# H_Power_feed.net
KiCad netlist of a schematic drawn in EAGLE
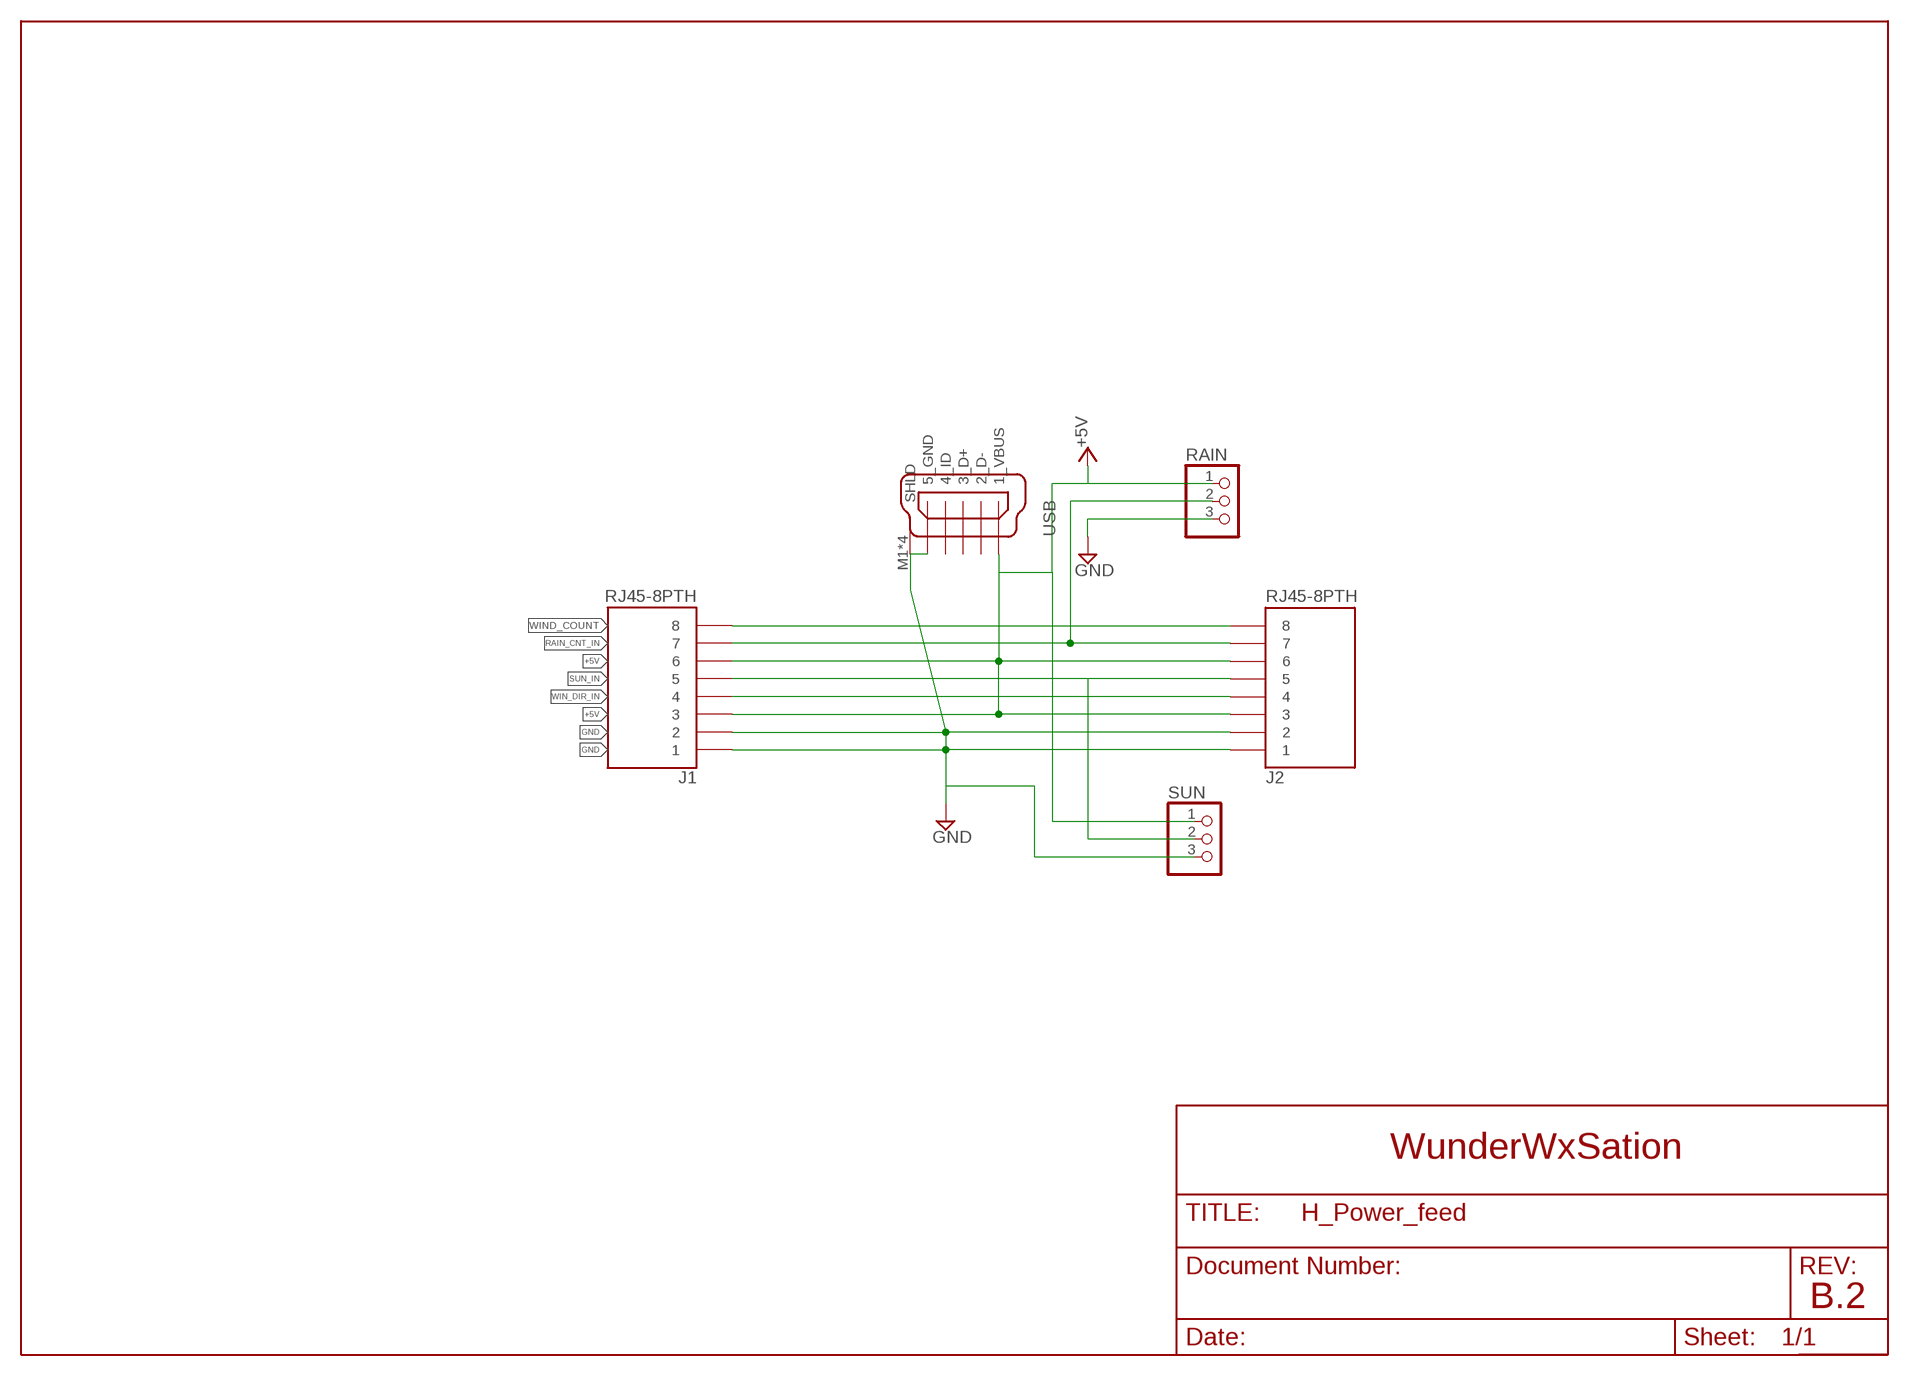
[diagram p0: schematic, sheet 1]

(export (version "E")
  (design (tool "Eeschema 10.0.6"))
  (components
    (comp (ref "J1")
      (value "RJ45-8PTH")
      (footprint "eagle-import:RJ45-8")
      (libsource (lib "eagle-import") (part "RJ45-8PTH"))
    )
    (comp (ref "J2")
      (value "RJ45-8PTH")
      (footprint "eagle-import:RJ45-8")
      (libsource (lib "eagle-import") (part "RJ45-8PTH"))
    )
    (comp (ref "RAIN")
      (value "PINHD-1X3MOLEX_KK")
      (footprint "eagle-import:1X3_MOLEX_KK")
      (libsource (lib "eagle-import") (part "PINHD-1X3MOLEX_KK"))
    )
    (comp (ref "SUN")
      (value "PINHD-1X3MOLEX_KK")
      (footprint "eagle-import:1X3_MOLEX_KK")
      (libsource (lib "eagle-import") (part "PINHD-1X3MOLEX_KK"))
    )
    (comp (ref "USB")
      (value "MINI-USB-32005-301")
      (footprint "eagle-import:32005-301")
      (libsource (lib "eagle-import") (part "MINI-USB-32005-301"))
    )
  )
  (nets
    (net (code "1") (name "+5V") (class "Default")
      (node (ref "J1") (pin "3") (pinfunction "3_3") (pintype "bidirectional"))
      (node (ref "J1") (pin "6") (pinfunction "6_6") (pintype "bidirectional"))
      (node (ref "J2") (pin "3") (pinfunction "3_3") (pintype "bidirectional"))
      (node (ref "J2") (pin "6") (pinfunction "6_6") (pintype "bidirectional"))
      (node (ref "RAIN") (pin "1") (pinfunction "1_1") (pintype "passive"))
      (node (ref "SUN") (pin "1") (pinfunction "1_1") (pintype "passive"))
      (node (ref "USB") (pin "1_VBUS") (pinfunction "1_VBUS_1_VBUS") (pintype "passive"))
    )
    (net (code "2") (name "GND") (class "Default")
      (node (ref "J1") (pin "1") (pinfunction "1_1") (pintype "bidirectional"))
      (node (ref "J1") (pin "2") (pinfunction "2_2") (pintype "bidirectional"))
      (node (ref "J2") (pin "1") (pinfunction "1_1") (pintype "bidirectional"))
      (node (ref "J2") (pin "2") (pinfunction "2_2") (pintype "bidirectional"))
      (node (ref "RAIN") (pin "3") (pinfunction "3_3") (pintype "passive"))
      (node (ref "SUN") (pin "3") (pinfunction "3_3") (pintype "passive"))
      (node (ref "USB") (pin "5_USB_GND") (pinfunction "5_GND_5_USB_GND") (pintype "passive"))
      (node (ref "USB") (pin "M1") (pinfunction "SHLD_M1") (pintype "passive"))
      (node (ref "USB") (pin "M2") (pinfunction "SHLD_M2") (pintype "passive"))
      (node (ref "USB") (pin "M3") (pinfunction "SHLD_M3") (pintype "passive"))
      (node (ref "USB") (pin "M4") (pinfunction "SHLD_M4") (pintype "passive"))
    )
    (net (code "3") (name "RAIN_CNT_IN") (class "Default")
      (node (ref "J1") (pin "7") (pinfunction "7_7") (pintype "bidirectional"))
      (node (ref "J2") (pin "7") (pinfunction "7_7") (pintype "bidirectional"))
      (node (ref "RAIN") (pin "2") (pinfunction "2_2") (pintype "passive"))
    )
    (net (code "4") (name "SUN_IN") (class "Default")
      (node (ref "J1") (pin "5") (pinfunction "5_5") (pintype "bidirectional"))
      (node (ref "J2") (pin "5") (pinfunction "5_5") (pintype "bidirectional"))
      (node (ref "SUN") (pin "2") (pinfunction "2_2") (pintype "passive"))
    )
    (net (code "5") (name "WIND_COUNT") (class "Default")
      (node (ref "J1") (pin "8") (pinfunction "8_8") (pintype "bidirectional"))
      (node (ref "J2") (pin "8") (pinfunction "8_8") (pintype "bidirectional"))
    )
    (net (code "6") (name "WIN_DIR_IN") (class "Default")
      (node (ref "J1") (pin "4") (pinfunction "4_4") (pintype "bidirectional"))
      (node (ref "J2") (pin "4") (pinfunction "4_4") (pintype "bidirectional"))
    )
    (net (code "7") (name "unconnected-(USB-Pad2_D-)") (class "Default")
      (node (ref "USB") (pin "2_D-") (pinfunction "2_D-_2_D-") (pintype "passive"))
    )
    (net (code "8") (name "unconnected-(USB-Pad3_D+)") (class "Default")
      (node (ref "USB") (pin "3_D+") (pinfunction "3_D+_3_D+") (pintype "passive"))
    )
    (net (code "9") (name "unconnected-(USB-Pad4_ID)") (class "Default")
      (node (ref "USB") (pin "4_ID") (pinfunction "4_ID_4_ID") (pintype "passive"))
    )
  )
)
